# Microcontroller.net
KiCad netlist of a schematic drawn in Altium Designer
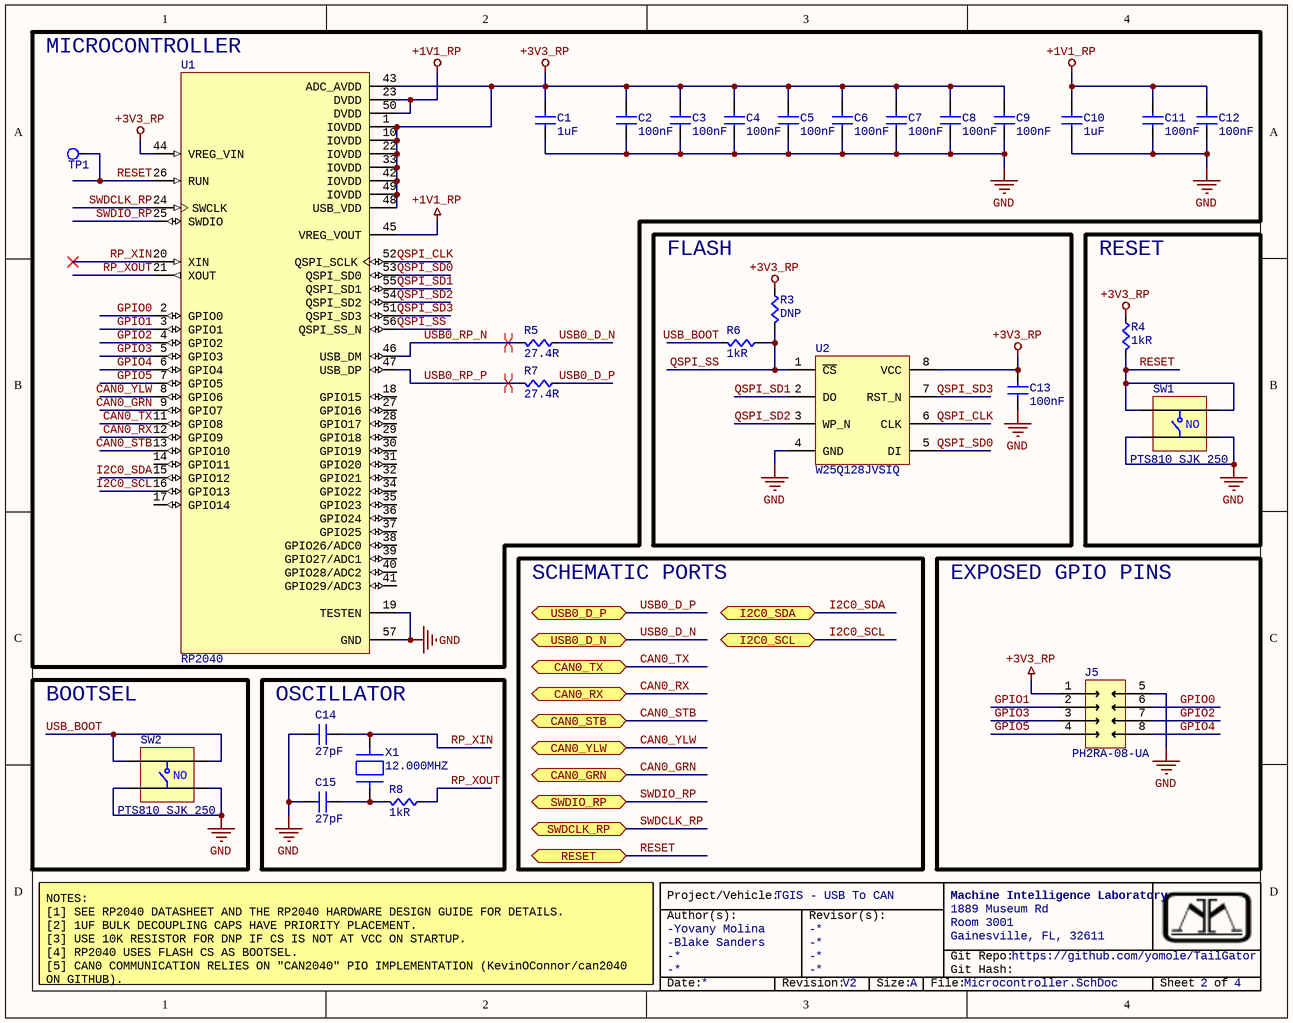
[diagram p0: Microcontroller.SchDoc]

(export (version "E")
  (design (tool "Eeschema 10.0.6"))
  (components
    (comp (ref "C1")
      (value "1uF")
      (footprint "CAPC0603")
      (description "Ceramic Capacitor, Multilayer, Cera")
      (fields (field (name "PART NUMBER") "CC0603KRX7R7BB105") (field (name "MANUFACTURER") "Yageo"))
      (libsource (lib "Parts") (part "NP_Capacitor"))
    )
    (comp (ref "C2")
      (value "100nF")
      (footprint "CAPC0603")
      (description "Ceramic Capacitor, Multilayer, Cera")
      (fields (field (name "PART NUMBER") "CC0603KRX7R7BB104") (field (name "MANUFACTURER") "Yageo"))
      (libsource (lib "Parts") (part "NP_Capacitor"))
    )
    (comp (ref "C3")
      (value "100nF")
      (footprint "CAPC0603")
      (description "Ceramic Capacitor, Multilayer, Cera")
      (fields (field (name "PART NUMBER") "CC0603KRX7R7BB104") (field (name "MANUFACTURER") "Yageo"))
      (libsource (lib "Parts") (part "NP_Capacitor"))
    )
    (comp (ref "C4")
      (value "100nF")
      (footprint "CAPC0603")
      (description "Ceramic Capacitor, Multilayer, Cera")
      (fields (field (name "PART NUMBER") "CC0603KRX7R7BB104") (field (name "MANUFACTURER") "Yageo"))
      (libsource (lib "Parts") (part "NP_Capacitor"))
    )
    (comp (ref "C5")
      (value "100nF")
      (footprint "CAPC0603")
      (description "Ceramic Capacitor, Multilayer, Cera")
      (fields (field (name "PART NUMBER") "CC0603KRX7R7BB104") (field (name "MANUFACTURER") "Yageo"))
      (libsource (lib "Parts") (part "NP_Capacitor"))
    )
    (comp (ref "C6")
      (value "100nF")
      (footprint "CAPC0603")
      (description "Ceramic Capacitor, Multilayer, Cera")
      (fields (field (name "PART NUMBER") "CC0603KRX7R7BB104") (field (name "MANUFACTURER") "Yageo"))
      (libsource (lib "Parts") (part "NP_Capacitor"))
    )
    (comp (ref "C7")
      (value "100nF")
      (footprint "CAPC0603")
      (description "Ceramic Capacitor, Multilayer, Cera")
      (fields (field (name "PART NUMBER") "CC0603KRX7R7BB104") (field (name "MANUFACTURER") "Yageo"))
      (libsource (lib "Parts") (part "NP_Capacitor"))
    )
    (comp (ref "C8")
      (value "100nF")
      (footprint "CAPC0603")
      (description "Ceramic Capacitor, Multilayer, Cera")
      (fields (field (name "PART NUMBER") "CC0603KRX7R7BB104") (field (name "MANUFACTURER") "Yageo"))
      (libsource (lib "Parts") (part "NP_Capacitor"))
    )
    (comp (ref "C9")
      (value "100nF")
      (footprint "CAPC0603")
      (description "Ceramic Capacitor, Multilayer, Cera")
      (fields (field (name "PART NUMBER") "CC0603KRX7R7BB104") (field (name "MANUFACTURER") "Yageo"))
      (libsource (lib "Parts") (part "NP_Capacitor"))
    )
    (comp (ref "C10")
      (value "1uF")
      (footprint "CAPC0603")
      (description "Ceramic Capacitor, Multilayer, Cera")
      (fields (field (name "PART NUMBER") "CC0603KRX7R7BB105") (field (name "MANUFACTURER") "Yageo"))
      (libsource (lib "Parts") (part "NP_Capacitor"))
    )
    (comp (ref "C11")
      (value "100nF")
      (footprint "CAPC0603")
      (description "Ceramic Capacitor, Multilayer, Cera")
      (fields (field (name "PART NUMBER") "CC0603KRX7R7BB104") (field (name "MANUFACTURER") "Yageo"))
      (libsource (lib "Parts") (part "NP_Capacitor"))
    )
    (comp (ref "C12")
      (value "100nF")
      (footprint "CAPC0603")
      (description "Ceramic Capacitor, Multilayer, Cera")
      (fields (field (name "PART NUMBER") "CC0603KRX7R7BB104") (field (name "MANUFACTURER") "Yageo"))
      (libsource (lib "Parts") (part "NP_Capacitor"))
    )
    (comp (ref "C13")
      (value "100nF")
      (footprint "CAPC0603")
      (description "Ceramic Capacitor, Multilayer, Cera")
      (fields (field (name "PART NUMBER") "CC0603KRX7R7BB104") (field (name "MANUFACTURER") "Yageo"))
      (libsource (lib "Parts") (part "NP_Capacitor"))
    )
    (comp (ref "C14")
      (value "27pF")
      (footprint "CAPC0603")
      (description "Ceramic Capacitor, Multilayer, Cera")
      (fields (field (name "PART NUMBER") "CC0603JRNPO9BN270") (field (name "MANUFACTURER") "Yageo"))
      (libsource (lib "Parts") (part "NP_Capacitor"))
    )
    (comp (ref "C15")
      (value "27pF")
      (footprint "CAPC0603")
      (description "Ceramic Capacitor, Multilayer, Cera")
      (fields (field (name "PART NUMBER") "CC0603JRNPO9BN270") (field (name "MANUFACTURER") "Yageo"))
      (libsource (lib "Parts") (part "NP_Capacitor"))
    )
    (comp (ref "J5")
      (value "PH2RA-08-UA")
      (footprint "PH2RA-08-UA")
      (description "Connector Header Through Hole, Right Angle 8 position 0.100\" (2.54mm)")
      (libsource (lib "TGIS") (part "PH2RA-08-UA"))
    )
    (comp (ref "R3")
      (value "DNP")
      (footprint "RES0603")
      (fields (field (name "Comment") "Res"))
      (libsource (lib "Passives") (part "Res"))
    )
    (comp (ref "R4")
      (value "1kR")
      (footprint "RES0603")
      (description "Fixed Resistor, Metal Glaze/thick F")
      (fields (field (name "PART NUMBER") "RC0603FR-071KL") (field (name "POWER") "100mW"))
      (libsource (lib "Parts") (part "Resistor"))
    )
    (comp (ref "R5")
      (value "27.4R")
      (footprint "RES0603")
      (description "Fixed Resistor, Metal Glaze/thick F")
      (fields (field (name "PART NUMBER") "RC0603FR-0727R4L") (field (name "POWER") "100mW"))
      (libsource (lib "Parts") (part "Resistor"))
    )
    (comp (ref "R6")
      (value "1kR")
      (footprint "RES0603")
      (description "Fixed Resistor, Metal Glaze/thick F")
      (fields (field (name "PART NUMBER") "RC0603FR-071KL") (field (name "POWER") "100mW"))
      (libsource (lib "Parts") (part "Resistor"))
    )
    (comp (ref "R7")
      (value "27.4R")
      (footprint "RES0603")
      (description "Fixed Resistor, Metal Glaze/thick F")
      (fields (field (name "PART NUMBER") "RC0603FR-0727R4L") (field (name "POWER") "100mW"))
      (libsource (lib "Parts") (part "Resistor"))
    )
    (comp (ref "R8")
      (value "1kR")
      (footprint "RES0603")
      (description "Fixed Resistor, Metal Glaze/thick F")
      (fields (field (name "PART NUMBER") "RC0603FR-071KL") (field (name "POWER") "100mW"))
      (libsource (lib "Parts") (part "Resistor"))
    )
    (comp (ref "SW1")
      (value "PTS810 SJK 250")
      (footprint "SW_PTS810_SJM_250_SMTR_LFS")
      (description "Tactile Switch SPST-NO Top Actuated Surface Mount")
      (libsource (lib "TGIS_Microcontrollers") (part "PTS810 SJK 250 SMTR LFS"))
    )
    (comp (ref "SW2")
      (value "PTS810 SJK 250")
      (footprint "SW_PTS810_SJM_250_SMTR_LFS")
      (description "Tactile Switch SPST-NO Top Actuated Surface Mount")
      (libsource (lib "TGIS_Microcontrollers") (part "PTS810 SJK 250 SMTR LFS"))
    )
    (comp (ref "TP1") (value "TP") (footprint "TPAD-60MIL") (libsource (lib "TGIS") (part "TP")))
    (comp (ref "U1")
      (value "RP2040")
      (footprint "QFN40P700X700X90-57N")
      (description "ARM® Cortex®-M0+ - Microcontroller IC 32-Bit Dual-Core 133MHz External Program Memory 56-QFN (7x7)")
      (fields (field (name "MF") "Raspberry Pi") (field (name "MP") "SC0914(13)"))
      (libsource (lib "TGIS_Microcontrollers") (part "SC0914(13)"))
    )
    (comp (ref "U2")
      (value "W25Q128JVSIQ")
      (footprint "SOIC127P790X216-8N")
      (description "FLASH - NOR Memory IC 128Mbit SPI - Quad I/O, QPI, DTR 133 MHz 8-SOIC")
      (libsource (lib "TGIS_Microcontrollers") (part "W25Q128JVSIQ"))
    )
    (comp (ref "X1")
      (value "12.000MHZ")
      (footprint "ABLS-12.000MHZ")
      (description "12 MHz ±20ppm Crystal 18pF 50 Ohms HC-49/US")
      (libsource (lib "TGIS_Microcontrollers") (part "ABLS-12.000MHZ"))
    )
  )
  (nets
    (net (code "1") (name "+1V1_RP") (class "Default")
      (node (ref "C10") (pin "2") (pinfunction "B_2") (pintype "passive"))
      (node (ref "C11") (pin "2") (pinfunction "B_2") (pintype "passive"))
      (node (ref "C12") (pin "2") (pinfunction "B_2") (pintype "passive"))
      (node (ref "U1") (pin "23") (pinfunction "DVDD_23") (pintype "power_in"))
      (node (ref "U1") (pin "45") (pinfunction "VREG_VOUT_45") (pintype "power_in"))
      (node (ref "U1") (pin "50") (pinfunction "DVDD_50") (pintype "power_in"))
    )
    (net (code "2") (name "+3V3_RP") (class "Default")
      (node (ref "C1") (pin "2") (pinfunction "B_2") (pintype "passive"))
      (node (ref "C13") (pin "2") (pinfunction "B_2") (pintype "passive"))
      (node (ref "C2") (pin "2") (pinfunction "B_2") (pintype "passive"))
      (node (ref "C3") (pin "2") (pinfunction "B_2") (pintype "passive"))
      (node (ref "C4") (pin "2") (pinfunction "B_2") (pintype "passive"))
      (node (ref "C5") (pin "2") (pinfunction "B_2") (pintype "passive"))
      (node (ref "C6") (pin "2") (pinfunction "B_2") (pintype "passive"))
      (node (ref "C7") (pin "2") (pinfunction "B_2") (pintype "passive"))
      (node (ref "C8") (pin "2") (pinfunction "B_2") (pintype "passive"))
      (node (ref "C9") (pin "2") (pinfunction "B_2") (pintype "passive"))
      (node (ref "J5") (pin "1") (pinfunction "1_1") (pintype "passive"))
      (node (ref "R3") (pin "2") (pinfunction "B_2") (pintype "passive"))
      (node (ref "R4") (pin "2") (pinfunction "B_2") (pintype "passive"))
      (node (ref "U1") (pin "1") (pinfunction "IOVDD_1") (pintype "power_in"))
      (node (ref "U1") (pin "10") (pinfunction "IOVDD_10") (pintype "power_in"))
      (node (ref "U1") (pin "22") (pinfunction "IOVDD_22") (pintype "power_in"))
      (node (ref "U1") (pin "33") (pinfunction "IOVDD_33") (pintype "power_in"))
      (node (ref "U1") (pin "42") (pinfunction "IOVDD_42") (pintype "power_in"))
      (node (ref "U1") (pin "43") (pinfunction "ADC_AVDD_43") (pintype "power_in"))
      (node (ref "U1") (pin "44") (pinfunction "VREG_VIN_44") (pintype "input"))
      (node (ref "U1") (pin "48") (pinfunction "USB_VDD_48") (pintype "power_in"))
      (node (ref "U1") (pin "49") (pinfunction "IOVDD_49") (pintype "power_in"))
      (node (ref "U2") (pin "8") (pinfunction "VCC_8") (pintype "passive"))
    )
    (net (code "3") (name "/CAN0_GRN") (class "Default")
      (node (ref "U1") (pin "9") (pinfunction "GPIO7_9") (pintype "bidirectional"))
    )
    (net (code "4") (name "/CAN0_RX") (class "Default")
      (node (ref "U1") (pin "12") (pinfunction "GPIO9_12") (pintype "bidirectional"))
    )
    (net (code "5") (name "/CAN0_STB") (class "Default")
      (node (ref "U1") (pin "13") (pinfunction "GPIO10_13") (pintype "bidirectional"))
    )
    (net (code "6") (name "/CAN0_TX") (class "Default")
      (node (ref "U1") (pin "11") (pinfunction "GPIO8_11") (pintype "bidirectional"))
    )
    (net (code "7") (name "/CAN0_YLW") (class "Default")
      (node (ref "U1") (pin "8") (pinfunction "GPIO6_8") (pintype "bidirectional"))
    )
    (net (code "8") (name "/GPIO0") (class "Default")
      (node (ref "J5") (pin "6") (pinfunction "6_6") (pintype "passive"))
      (node (ref "U1") (pin "2") (pinfunction "GPIO0_2") (pintype "bidirectional"))
    )
    (net (code "9") (name "/GPIO1") (class "Default")
      (node (ref "J5") (pin "2") (pinfunction "2_2") (pintype "passive"))
      (node (ref "U1") (pin "3") (pinfunction "GPIO1_3") (pintype "bidirectional"))
    )
    (net (code "10") (name "/GPIO2") (class "Default")
      (node (ref "J5") (pin "7") (pinfunction "7_7") (pintype "passive"))
      (node (ref "U1") (pin "4") (pinfunction "GPIO2_4") (pintype "bidirectional"))
    )
    (net (code "11") (name "/GPIO3") (class "Default")
      (node (ref "J5") (pin "3") (pinfunction "3_3") (pintype "passive"))
      (node (ref "U1") (pin "5") (pinfunction "GPIO3_5") (pintype "bidirectional"))
    )
    (net (code "12") (name "/GPIO4") (class "Default")
      (node (ref "J5") (pin "8") (pinfunction "8_8") (pintype "passive"))
      (node (ref "U1") (pin "6") (pinfunction "GPIO4_6") (pintype "bidirectional"))
    )
    (net (code "13") (name "/GPIO5") (class "Default")
      (node (ref "J5") (pin "4") (pinfunction "4_4") (pintype "passive"))
      (node (ref "U1") (pin "7") (pinfunction "GPIO5_7") (pintype "bidirectional"))
    )
    (net (code "14") (name "/I2C0_SCL") (class "Default")
      (node (ref "U1") (pin "16") (pinfunction "GPIO13_16") (pintype "bidirectional"))
    )
    (net (code "15") (name "/I2C0_SDA") (class "Default")
      (node (ref "U1") (pin "15") (pinfunction "GPIO12_15") (pintype "bidirectional"))
    )
    (net (code "16") (name "/QSPI_CLK") (class "Default")
      (node (ref "U1") (pin "52") (pinfunction "QSPI_SCLK_52") (pintype "bidirectional"))
      (node (ref "U2") (pin "6") (pinfunction "CLK_6") (pintype "passive"))
    )
    (net (code "17") (name "/QSPI_SD0") (class "Default")
      (node (ref "U1") (pin "53") (pinfunction "QSPI_SD0_53") (pintype "bidirectional"))
      (node (ref "U2") (pin "5") (pinfunction "DI_5") (pintype "passive"))
    )
    (net (code "18") (name "/QSPI_SD1") (class "Default")
      (node (ref "U1") (pin "55") (pinfunction "QSPI_SD1_55") (pintype "bidirectional"))
      (node (ref "U2") (pin "2") (pinfunction "DO_2") (pintype "passive"))
    )
    (net (code "19") (name "/QSPI_SD2") (class "Default")
      (node (ref "U1") (pin "54") (pinfunction "QSPI_SD2_54") (pintype "bidirectional"))
      (node (ref "U2") (pin "3") (pinfunction "WP_N_3") (pintype "passive"))
    )
    (net (code "20") (name "/QSPI_SD3") (class "Default")
      (node (ref "U1") (pin "51") (pinfunction "QSPI_SD3_51") (pintype "bidirectional"))
      (node (ref "U2") (pin "7") (pinfunction "RST_N_7") (pintype "passive"))
    )
    (net (code "21") (name "/QSPI_SS") (class "Default")
      (node (ref "R3") (pin "1") (pinfunction "A_1") (pintype "passive"))
      (node (ref "R6") (pin "2") (pinfunction "B_2") (pintype "passive"))
      (node (ref "U1") (pin "56") (pinfunction "QSPI_SS_N_56") (pintype "bidirectional"))
      (node (ref "U2") (pin "1") (pinfunction "CS_1") (pintype "passive"))
    )
    (net (code "22") (name "/RESET") (class "Default")
      (node (ref "R4") (pin "1") (pinfunction "A_1") (pintype "passive"))
      (node (ref "SW1") (pin "1") (pinfunction "1_1") (pintype "passive"))
      (node (ref "SW1") (pin "2") (pinfunction "2_2") (pintype "passive"))
      (node (ref "TP1") (pin "1") (pinfunction "1_1") (pintype "passive"))
      (node (ref "U1") (pin "26") (pinfunction "RUN_26") (pintype "input"))
    )
    (net (code "23") (name "/RP_XIN") (class "Default")
      (node (ref "C14") (pin "2") (pinfunction "B_2") (pintype "passive"))
      (node (ref "U1") (pin "20") (pinfunction "XIN_20") (pintype "input"))
      (node (ref "X1") (pin "2") (pinfunction "2_2") (pintype "passive"))
    )
    (net (code "24") (name "/RP_XOUT") (class "Default")
      (node (ref "R8") (pin "2") (pinfunction "B_2") (pintype "passive"))
      (node (ref "U1") (pin "21") (pinfunction "XOUT_21") (pintype "output"))
    )
    (net (code "25") (name "/SWDCLK_RP") (class "Default")
      (node (ref "U1") (pin "24") (pinfunction "SWCLK_24") (pintype "input"))
    )
    (net (code "26") (name "/SWDIO_RP") (class "Default")
      (node (ref "U1") (pin "25") (pinfunction "SWDIO_25") (pintype "bidirectional"))
    )
    (net (code "27") (name "/USB0_D_N") (class "Default")
      (node (ref "R5") (pin "2") (pinfunction "B_2") (pintype "passive"))
    )
    (net (code "28") (name "/USB0_D_P") (class "Default")
      (node (ref "R7") (pin "2") (pinfunction "B_2") (pintype "passive"))
    )
    (net (code "29") (name "/USB0_RP_N") (class "Default")
      (node (ref "R5") (pin "1") (pinfunction "A_1") (pintype "passive"))
      (node (ref "U1") (pin "46") (pinfunction "USB_DM_46") (pintype "bidirectional"))
    )
    (net (code "30") (name "/USB0_RP_P") (class "Default")
      (node (ref "R7") (pin "1") (pinfunction "A_1") (pintype "passive"))
      (node (ref "U1") (pin "47") (pinfunction "USB_DP_47") (pintype "bidirectional"))
    )
    (net (code "31") (name "/USB_BOOT") (class "Default")
      (node (ref "R6") (pin "1") (pinfunction "A_1") (pintype "passive"))
      (node (ref "SW2") (pin "1") (pinfunction "1_1") (pintype "passive"))
      (node (ref "SW2") (pin "2") (pinfunction "2_2") (pintype "passive"))
    )
    (net (code "32") (name "GND") (class "Default")
      (node (ref "C1") (pin "1") (pinfunction "A_1") (pintype "passive"))
      (node (ref "C10") (pin "1") (pinfunction "A_1") (pintype "passive"))
      (node (ref "C11") (pin "1") (pinfunction "A_1") (pintype "passive"))
      (node (ref "C12") (pin "1") (pinfunction "A_1") (pintype "passive"))
      (node (ref "C13") (pin "1") (pinfunction "A_1") (pintype "passive"))
      (node (ref "C14") (pin "1") (pinfunction "A_1") (pintype "passive"))
      (node (ref "C15") (pin "1") (pinfunction "A_1") (pintype "passive"))
      (node (ref "C2") (pin "1") (pinfunction "A_1") (pintype "passive"))
      (node (ref "C3") (pin "1") (pinfunction "A_1") (pintype "passive"))
      (node (ref "C4") (pin "1") (pinfunction "A_1") (pintype "passive"))
      (node (ref "C5") (pin "1") (pinfunction "A_1") (pintype "passive"))
      (node (ref "C6") (pin "1") (pinfunction "A_1") (pintype "passive"))
      (node (ref "C7") (pin "1") (pinfunction "A_1") (pintype "passive"))
      (node (ref "C8") (pin "1") (pinfunction "A_1") (pintype "passive"))
      (node (ref "C9") (pin "1") (pinfunction "A_1") (pintype "passive"))
      (node (ref "J5") (pin "5") (pinfunction "5_5") (pintype "passive"))
      (node (ref "SW1") (pin "3") (pinfunction "3_3") (pintype "passive"))
      (node (ref "SW1") (pin "4") (pinfunction "4_4") (pintype "passive"))
      (node (ref "SW2") (pin "3") (pinfunction "3_3") (pintype "passive"))
      (node (ref "SW2") (pin "4") (pinfunction "4_4") (pintype "passive"))
      (node (ref "U1") (pin "19") (pinfunction "TESTEN_19") (pintype "passive"))
      (node (ref "U1") (pin "57") (pinfunction "GND_57") (pintype "power_in"))
      (node (ref "U2") (pin "4") (pinfunction "GND_4") (pintype "passive"))
    )
    (net (code "33") (name "Net-(C15-B)") (class "Default")
      (node (ref "C15") (pin "2") (pinfunction "B_2") (pintype "passive"))
      (node (ref "R8") (pin "1") (pinfunction "A_1") (pintype "passive"))
      (node (ref "X1") (pin "1") (pinfunction "1_1") (pintype "passive"))
    )
    (net (code "34") (name "unconnected-(U1-GPIO11-Pad14)") (class "Default")
      (node (ref "U1") (pin "14") (pinfunction "GPIO11_14") (pintype "bidirectional"))
    )
    (net (code "35") (name "unconnected-(U1-GPIO14-Pad17)") (class "Default")
      (node (ref "U1") (pin "17") (pinfunction "GPIO14_17") (pintype "bidirectional"))
    )
    (net (code "36") (name "unconnected-(U1-GPIO15-Pad18)") (class "Default")
      (node (ref "U1") (pin "18") (pinfunction "GPIO15_18") (pintype "bidirectional"))
    )
    (net (code "37") (name "unconnected-(U1-GPIO16-Pad27)") (class "Default")
      (node (ref "U1") (pin "27") (pinfunction "GPIO16_27") (pintype "bidirectional"))
    )
    (net (code "38") (name "unconnected-(U1-GPIO17-Pad28)") (class "Default")
      (node (ref "U1") (pin "28") (pinfunction "GPIO17_28") (pintype "bidirectional"))
    )
    (net (code "39") (name "unconnected-(U1-GPIO18-Pad29)") (class "Default")
      (node (ref "U1") (pin "29") (pinfunction "GPIO18_29") (pintype "bidirectional"))
    )
    (net (code "40") (name "unconnected-(U1-GPIO19-Pad30)") (class "Default")
      (node (ref "U1") (pin "30") (pinfunction "GPIO19_30") (pintype "bidirectional"))
    )
    (net (code "41") (name "unconnected-(U1-GPIO20-Pad31)") (class "Default")
      (node (ref "U1") (pin "31") (pinfunction "GPIO20_31") (pintype "bidirectional"))
    )
    (net (code "42") (name "unconnected-(U1-GPIO21-Pad32)") (class "Default")
      (node (ref "U1") (pin "32") (pinfunction "GPIO21_32") (pintype "bidirectional"))
    )
    (net (code "43") (name "unconnected-(U1-GPIO22-Pad34)") (class "Default")
      (node (ref "U1") (pin "34") (pinfunction "GPIO22_34") (pintype "bidirectional"))
    )
    (net (code "44") (name "unconnected-(U1-GPIO23-Pad35)") (class "Default")
      (node (ref "U1") (pin "35") (pinfunction "GPIO23_35") (pintype "bidirectional"))
    )
    (net (code "45") (name "unconnected-(U1-GPIO24-Pad36)") (class "Default")
      (node (ref "U1") (pin "36") (pinfunction "GPIO24_36") (pintype "bidirectional"))
    )
    (net (code "46") (name "unconnected-(U1-GPIO25-Pad37)") (class "Default")
      (node (ref "U1") (pin "37") (pinfunction "GPIO25_37") (pintype "bidirectional"))
    )
    (net (code "47") (name "unconnected-(U1-GPIO26{slash}ADC0-Pad38)") (class "Default")
      (node (ref "U1") (pin "38") (pinfunction "GPIO26/ADC0_38") (pintype "bidirectional"))
    )
    (net (code "48") (name "unconnected-(U1-GPIO27{slash}ADC1-Pad39)") (class "Default")
      (node (ref "U1") (pin "39") (pinfunction "GPIO27/ADC1_39") (pintype "bidirectional"))
    )
    (net (code "49") (name "unconnected-(U1-GPIO28{slash}ADC2-Pad40)") (class "Default")
      (node (ref "U1") (pin "40") (pinfunction "GPIO28/ADC2_40") (pintype "bidirectional"))
    )
    (net (code "50") (name "unconnected-(U1-GPIO29{slash}ADC3-Pad41)") (class "Default")
      (node (ref "U1") (pin "41") (pinfunction "GPIO29/ADC3_41") (pintype "bidirectional"))
    )
  )
)
